# EFUSE_TPS259250.net
KiCad netlist of a schematic drawn in Altium Designer
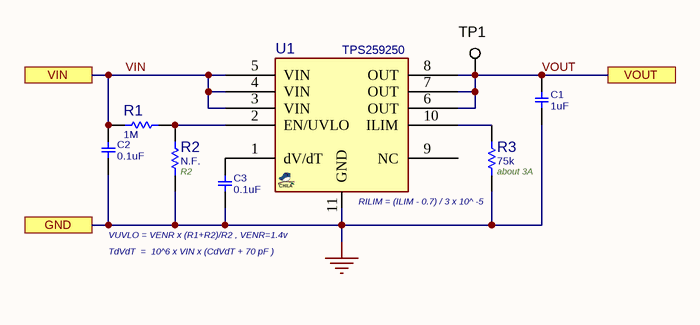
[diagram p0: EFUSE_TPS259250.SchDoc]

(export (version "E")
  (design (tool "Eeschema 10.0.6"))
  (components
    (comp (ref "C1")
      (value "1uF")
      (footprint "C0402")
      (description "CAP, MLCC")
      (fields (field (name "MANF_P#") "CL05A105KO5NNND") (field (name "MANF") "Samsung"))
      (libsource (lib "passive_smd") (part "CAP_SMD_MLCC"))
    )
    (comp (ref "C2")
      (value "0.1uF")
      (footprint "C0402")
      (description "CAP, MLCC")
      (fields (field (name "MANF_P#") "GRM155R71H104KE14D") (field (name "MANF") "Murata"))
      (libsource (lib "passive_smd") (part "CAP_SMD_MLCC"))
    )
    (comp (ref "C3")
      (value "0.1uF")
      (footprint "C0402")
      (description "CAP, MLCC")
      (fields (field (name "MANF_P#") "GRM155R71H104KE14D") (field (name "MANF") "Murata"))
      (libsource (lib "passive_smd") (part "CAP_SMD_MLCC"))
    )
    (comp (ref "R1")
      (value "1M")
      (footprint "R0402")
      (description "RESISTOR, SMD")
      (libsource (lib "passive_res_smd") (part "RES_SMD"))
    )
    (comp (ref "R2")
      (value "N.F.")
      (footprint "R0402")
      (description "RESISTOR, SMD")
      (libsource (lib "passive_res_smd") (part "RES_SMD"))
    )
    (comp (ref "R3")
      (value "75k")
      (footprint "R0402")
      (description "RESISTOR, SMD")
      (libsource (lib "passive_res_smd") (part "RES_SMD"))
    )
    (comp (ref "TP1")
      (value "TESTPOINT_SMD")
      (footprint "TPSMD_S1")
      (description "TEST POINT")
      (fields (field (name "MANF") "MANF") (field (name "MANF_P#") "MANF_P#"))
      (libsource (lib "test-tp_jumper") (part "TESTPOINT_SMD"))
    )
    (comp (ref "U1")
      (value "TPS259250")
      (footprint "SON50_10T_3030")
      (description "LOAD SW, 5V eFuse, 5A, 4.5~5.5V, 30mOhm")
      (fields (field (name "MANF") "TI") (field (name "MANF_P#") "TPS259250DRCR, TPS259250DRCT"))
      (libsource (lib "power_load_switch") (part "TPS259250_SON10"))
    )
  )
  (nets
    (net (code "1") (name "/VIN") (class "Default")
      (node (ref "C2") (pin "2") (pinfunction "2_2") (pintype "passive"))
      (node (ref "R1") (pin "1") (pinfunction "1_1") (pintype "passive"))
      (node (ref "U1") (pin "3") (pinfunction "VIN_3") (pintype "passive"))
      (node (ref "U1") (pin "4") (pinfunction "VIN_4") (pintype "passive"))
      (node (ref "U1") (pin "5") (pinfunction "VIN_5") (pintype "passive"))
    )
    (net (code "2") (name "/VOUT") (class "Default")
      (node (ref "C1") (pin "2") (pinfunction "2_2") (pintype "passive"))
      (node (ref "TP1") (pin "1") (pinfunction "1_1") (pintype "passive"))
      (node (ref "U1") (pin "6") (pinfunction "OUT_6") (pintype "passive"))
      (node (ref "U1") (pin "7") (pinfunction "OUT_7") (pintype "passive"))
      (node (ref "U1") (pin "8") (pinfunction "OUT_8") (pintype "passive"))
    )
    (net (code "3") (name "GND") (class "Default")
      (node (ref "C1") (pin "1") (pinfunction "1_1") (pintype "passive"))
      (node (ref "C2") (pin "1") (pinfunction "1_1") (pintype "passive"))
      (node (ref "C3") (pin "1") (pinfunction "1_1") (pintype "passive"))
      (node (ref "R2") (pin "1") (pinfunction "1_1") (pintype "passive"))
      (node (ref "R3") (pin "1") (pinfunction "1_1") (pintype "passive"))
      (node (ref "U1") (pin "11") (pinfunction "GND_11") (pintype "power_in"))
    )
    (net (code "4") (name "Net-(U1-EN{slash}UVLO)") (class "Default")
      (node (ref "R1") (pin "2") (pinfunction "2_2") (pintype "passive"))
      (node (ref "R2") (pin "2") (pinfunction "2_2") (pintype "passive"))
      (node (ref "U1") (pin "2") (pinfunction "EN/UVLO_2") (pintype "passive"))
    )
    (net (code "5") (name "Net-(U1-ILIM)") (class "Default")
      (node (ref "R3") (pin "2") (pinfunction "2_2") (pintype "passive"))
      (node (ref "U1") (pin "10") (pinfunction "ILIM_10") (pintype "passive"))
    )
    (net (code "6") (name "Net-(U1-dV{slash}dT)") (class "Default")
      (node (ref "C3") (pin "2") (pinfunction "2_2") (pintype "passive"))
      (node (ref "U1") (pin "1") (pinfunction "dV/dT_1") (pintype "passive"))
    )
    (net (code "7") (name "unconnected-(U1-NC-Pad9)") (class "Default")
      (node (ref "U1") (pin "9") (pinfunction "NC_9") (pintype "passive"))
    )
  )
)
